# Sheet1.net
KiCad netlist of a schematic drawn in Altium Designer
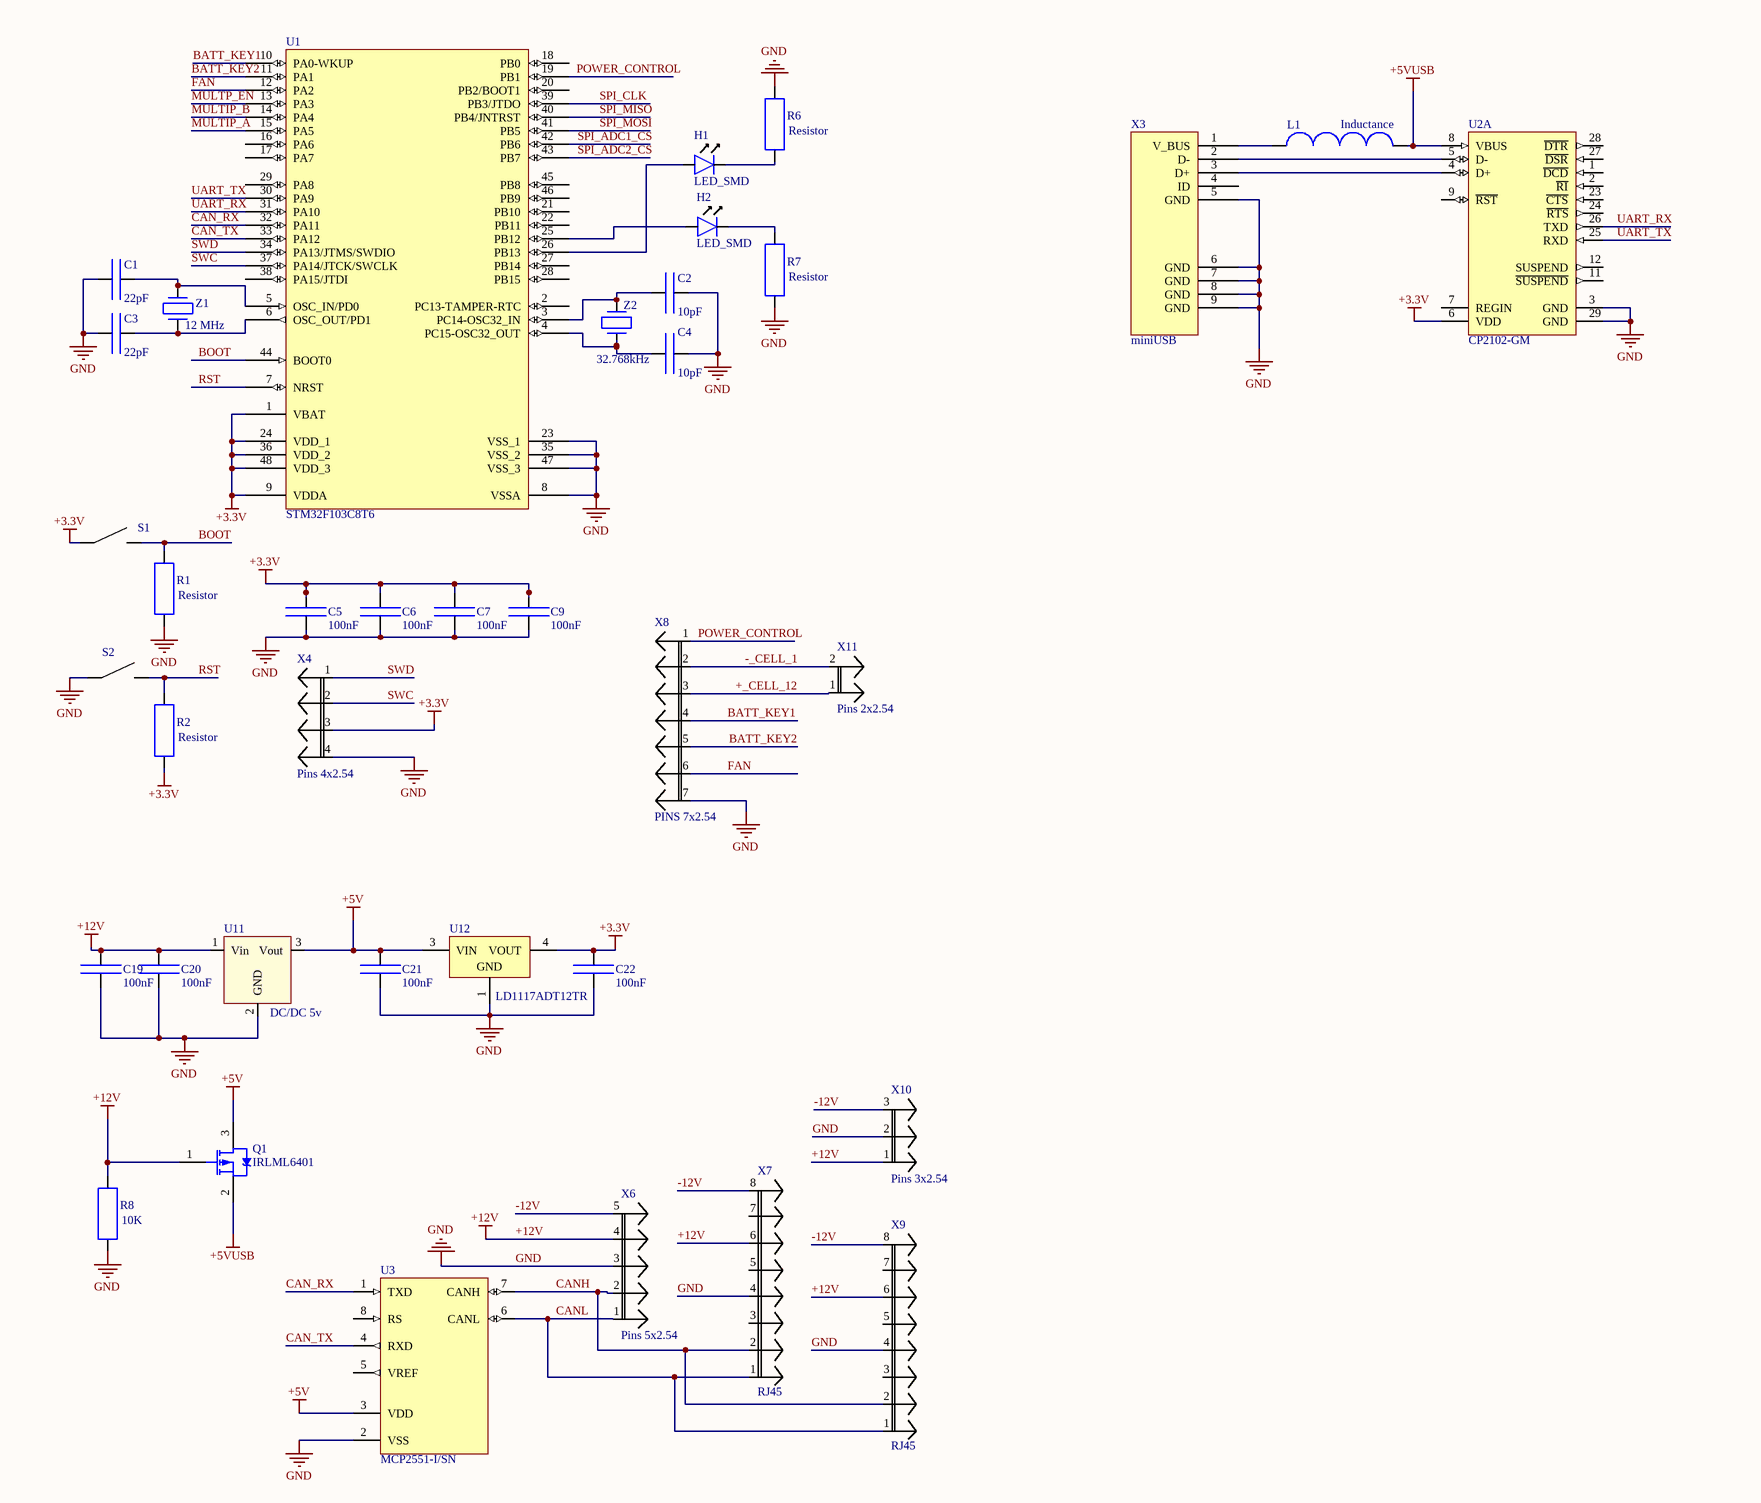
[diagram p0: Sheet1.SchDoc, top]
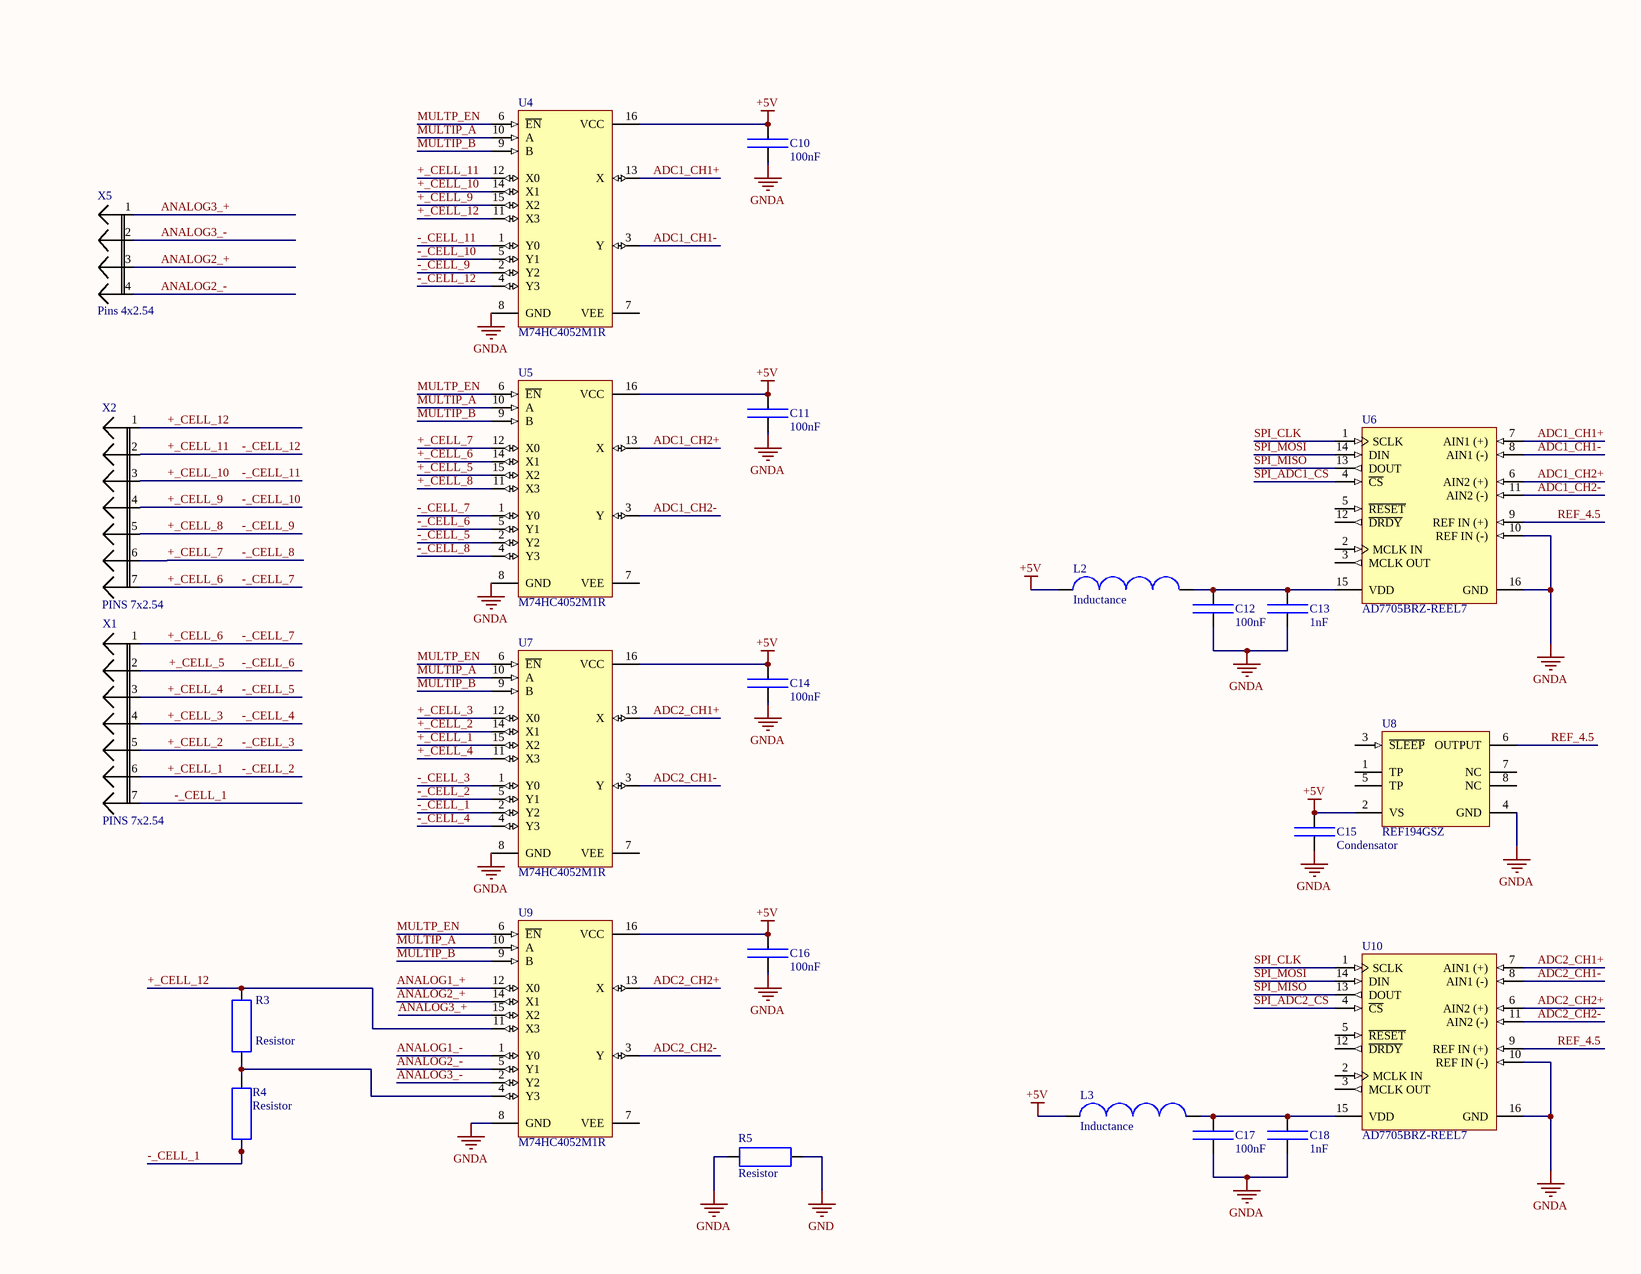
[diagram p1: Sheet1.SchDoc, bottom]

(export (version "E")
  (design (tool "Eeschema 10.0.6"))
  (components
    (comp (ref "C1") (value "22pF") (footprint "C0805") (libsource (lib "A_H_sch_lib") (part "Condensator")))
    (comp (ref "C2") (value "10pF") (footprint "C0805") (libsource (lib "A_H_sch_lib") (part "Condensator")))
    (comp (ref "C3") (value "22pF") (footprint "C0805") (libsource (lib "A_H_sch_lib") (part "Condensator")))
    (comp (ref "C4") (value "10pF") (footprint "C0805") (libsource (lib "A_H_sch_lib") (part "Condensator")))
    (comp (ref "C5") (value "100nF") (footprint "C0805") (libsource (lib "A_H_sch_lib") (part "Condensator")))
    (comp (ref "C6") (value "100nF") (footprint "C0805") (libsource (lib "A_H_sch_lib") (part "Condensator")))
    (comp (ref "C7") (value "100nF") (footprint "C0805") (libsource (lib "A_H_sch_lib") (part "Condensator")))
    (comp (ref "C9") (value "100nF") (footprint "C0805") (libsource (lib "A_H_sch_lib") (part "Condensator")))
    (comp (ref "C10")
      (value "100nF")
      (footprint "C0805")
      (libsource (lib "A_H_sch_lib") (part "Condensator"))
    )
    (comp (ref "C11")
      (value "100nF")
      (footprint "C0805")
      (libsource (lib "A_H_sch_lib") (part "Condensator"))
    )
    (comp (ref "C12")
      (value "100nF")
      (footprint "C0805")
      (libsource (lib "A_H_sch_lib") (part "Condensator"))
    )
    (comp (ref "C13") (value "1nF") (footprint "C0805") (libsource (lib "A_H_sch_lib") (part "Condensator")))
    (comp (ref "C14")
      (value "100nF")
      (footprint "C0805")
      (libsource (lib "A_H_sch_lib") (part "Condensator"))
    )
    (comp (ref "C15")
      (value "Condensator")
      (footprint "C0805")
      (libsource (lib "A_H_sch_lib") (part "Condensator"))
    )
    (comp (ref "C16")
      (value "100nF")
      (footprint "C0805")
      (libsource (lib "A_H_sch_lib") (part "Condensator"))
    )
    (comp (ref "C17")
      (value "100nF")
      (footprint "C0805")
      (libsource (lib "A_H_sch_lib") (part "Condensator"))
    )
    (comp (ref "C18") (value "1nF") (footprint "C0805") (libsource (lib "A_H_sch_lib") (part "Condensator")))
    (comp (ref "C19")
      (value "100nF")
      (footprint "C0805")
      (libsource (lib "A_H_sch_lib") (part "Condensator"))
    )
    (comp (ref "C20")
      (value "100nF")
      (footprint "C0805")
      (libsource (lib "A_H_sch_lib") (part "Condensator"))
    )
    (comp (ref "C21")
      (value "100nF")
      (footprint "C0805")
      (libsource (lib "A_H_sch_lib") (part "Condensator"))
    )
    (comp (ref "C22")
      (value "100nF")
      (footprint "C0805")
      (libsource (lib "A_H_sch_lib") (part "Condensator"))
    )
    (comp (ref "H1") (value "LED_SMD") (footprint "C0805") (libsource (lib "A_H_sch_lib") (part "LED_SMD")))
    (comp (ref "H2") (value "LED_SMD") (footprint "C0805") (libsource (lib "A_H_sch_lib") (part "LED_SMD")))
    (comp (ref "L1")
      (value "Inductance")
      (footprint "L0805")
      (libsource (lib "A_H_sch_lib") (part "Inductance"))
    )
    (comp (ref "L2")
      (value "Inductance")
      (footprint "L0805")
      (libsource (lib "A_H_sch_lib") (part "Inductance"))
    )
    (comp (ref "L3")
      (value "Inductance")
      (footprint "L0805")
      (libsource (lib "A_H_sch_lib") (part "Inductance"))
    )
    (comp (ref "Q1")
      (value "IRLML6401")
      (footprint "sot-23")
      (libsource (lib "A_H_sch_lib") (part "IRLML6401"))
    )
    (comp (ref "R1") (value "Resistor") (footprint "R0805") (libsource (lib "A_H_sch_lib") (part "Resistor")))
    (comp (ref "R2") (value "Resistor") (footprint "R0805") (libsource (lib "A_H_sch_lib") (part "Resistor")))
    (comp (ref "R3") (value "Resistor") (footprint "R0805") (libsource (lib "A_H_sch_lib") (part "Resistor")))
    (comp (ref "R4") (value "Resistor") (footprint "R0805") (libsource (lib "A_H_sch_lib") (part "Resistor")))
    (comp (ref "R5") (value "Resistor") (footprint "R0805") (libsource (lib "A_H_sch_lib") (part "Resistor")))
    (comp (ref "R6") (value "Resistor") (footprint "R0805") (libsource (lib "A_H_sch_lib") (part "Resistor")))
    (comp (ref "R7") (value "Resistor") (footprint "R0805") (libsource (lib "A_H_sch_lib") (part "Resistor")))
    (comp (ref "R8") (value "10K") (footprint "R0805") (libsource (lib "A_H_sch_lib") (part "Resistor")))
    (comp (ref "S1")
      (value "Tact_switch")
      (footprint "Tact_switch_smd")
      (libsource (lib "A_H_sch_lib") (part "Tact_switch"))
    )
    (comp (ref "S2")
      (value "Tact_switch")
      (footprint "Tact_switch_smd")
      (libsource (lib "A_H_sch_lib") (part "Tact_switch"))
    )
    (comp (ref "U1")
      (value "STM32F103C8T6")
      (footprint "LQFP48_N")
      (description "STM32 ARM-based 32-bit MCU with 64 Kbytes Flash, 48-pin LQFP, Industrial Temperature")
      (fields (field (name "PUBLISHER") "Altium Limited"))
      (libsource (lib "ST Microcontroller 32-Bit STM32") (part "STM32F103C8T6"))
    )
    (comp (ref "U2")
      (value "CP2102-GM")
      (footprint "SLAB-QFN-28-3125x3125TP_N")
      (description "Single-Chip USB to UART Bridge, 1024 Bytes EEPROM, -40 to 85 degC, 28-pin QFN, Tube")
      (fields (field (name "MANUFACTURER") "Silicon Labs"))
      (libsource (lib "Silicon Labs Interface") (part "CP2102-GM"))
    )
    (comp (ref "U3")
      (value "MCP2551-I/SN")
      (footprint "SOIC-SN8_N")
      (description "High-Speed CAN Transceiver, 8-Pin SOIC, Industrial Temperature")
      (fields (field (name "PUBLISHER") "Altium Limited"))
      (libsource (lib "Microchip Interface") (part "MCP2551-I/SN"))
    )
    (comp (ref "U4")
      (value "M74HC4052M1R")
      (footprint "SO16_N")
      (description "Analog Multiplexer/Demultiplexer Dual 4-Channel")
      (fields (field (name "PUBLISHER") "Altium Limited"))
      (libsource (lib "ST Logic Multiplexer") (part "M74HC4052M1R"))
    )
    (comp (ref "U5")
      (value "M74HC4052M1R")
      (footprint "SO16_N")
      (description "Analog Multiplexer/Demultiplexer Dual 4-Channel")
      (fields (field (name "PUBLISHER") "Altium Limited"))
      (libsource (lib "ST Logic Multiplexer") (part "M74HC4052M1R"))
    )
    (comp (ref "U6")
      (value "AD7705BRZ-REEL7")
      (footprint "RW-16_N")
      (fields (field (name "GENERIC PART NUMBER") "AD7705") (field (name "MANUFACTURER") "Analog Devices"))
      (libsource (lib "Analog Devices Data Converters Analog-to-Digital Converters") (part "AD7705BRZ-REEL7"))
    )
    (comp (ref "U7")
      (value "M74HC4052M1R")
      (footprint "SO16_N")
      (description "Analog Multiplexer/Demultiplexer Dual 4-Channel")
      (fields (field (name "PUBLISHER") "Altium Limited"))
      (libsource (lib "ST Logic Multiplexer") (part "M74HC4052M1R"))
    )
    (comp (ref "U8")
      (value "REF194GSZ")
      (footprint "ADI-R-8_N")
      (fields (field (name "MANUFACTURER") "Analog Devices"))
      (libsource (lib "Analog Devices Amplifiers and Linear Voltage References") (part "REF194GSZ"))
    )
    (comp (ref "U9")
      (value "M74HC4052M1R")
      (footprint "SO16_N")
      (description "Analog Multiplexer/Demultiplexer Dual 4-Channel")
      (fields (field (name "PUBLISHER") "Altium Limited"))
      (libsource (lib "ST Logic Multiplexer") (part "M74HC4052M1R"))
    )
    (comp (ref "U10")
      (value "AD7705BRZ-REEL7")
      (footprint "RW-16_N")
      (fields (field (name "GENERIC PART NUMBER") "AD7705") (field (name "MANUFACTURER") "Analog Devices"))
      (libsource (lib "Analog Devices Data Converters Analog-to-Digital Converters") (part "AD7705BRZ-REEL7"))
    )
    (comp (ref "U11")
      (value "DC/DC 5v")
      (footprint "A_H_pcb_lib:DC/DC R-78E")
      (libsource (lib "A_H_sch_lib") (part "DC/DC R-78E"))
    )
    (comp (ref "U12")
      (value "LD1117ADT12TR")
      (footprint "TO-252_N")
      (description "1A, Low Drop Positive Voltage Regulator, 1.2V, 3-Pin DPAK, Tape and Reel")
      (libsource (lib "STMicroelectronics Power Management Linear Regulator") (part "LD1117ADT12TR"))
    )
    (comp (ref "X1")
      (value "PINS 7x2.54")
      (footprint "A_H_pcb_lib:PINS 7X2.54")
      (libsource (lib "A_H_sch_lib") (part "PINS 7x2.54"))
    )
    (comp (ref "X2")
      (value "PINS 7x2.54")
      (footprint "A_H_pcb_lib:PINS 7X2.54")
      (libsource (lib "A_H_sch_lib") (part "PINS 7x2.54"))
    )
    (comp (ref "X3")
      (value "miniUSB")
      (footprint "A_H_pcb_lib:miniUSB")
      (libsource (lib "A_H_sch_lib") (part "miniUSB"))
    )
    (comp (ref "X4")
      (value "Pins 4x2.54")
      (footprint "Pins 4x2.54")
      (libsource (lib "A_H_sch_lib") (part "Pins 4x2.54"))
    )
    (comp (ref "X5")
      (value "Pins 4x2.54")
      (footprint "Pins 4x2.54")
      (libsource (lib "A_H_sch_lib") (part "Pins 4x2.54"))
    )
    (comp (ref "X6")
      (value "Pins 5x2.54")
      (footprint "Pins 5x2.54")
      (libsource (lib "A_H_sch_lib") (part "Pins 5x2.54"))
    )
    (comp (ref "X7")
      (value "RJ45")
      (footprint "A_H_pcb_lib:RJ45")
      (libsource (lib "A_H_sch_lib") (part "RJ45"))
    )
    (comp (ref "X8")
      (value "PINS 7x2.54")
      (footprint "PINS 7X2.54")
      (libsource (lib "") (part "PINS 7x2.54_1"))
    )
    (comp (ref "X9")
      (value "RJ45")
      (footprint "A_H_pcb_lib:RJ45")
      (libsource (lib "A_H_sch_lib") (part "RJ45"))
    )
    (comp (ref "X10")
      (value "Pins 3x2.54")
      (footprint "Pins 3x2.54")
      (libsource (lib "A_H_sch_lib") (part "Pins 3x2.54"))
    )
    (comp (ref "X11")
      (value "Pins 2x2.54")
      (footprint "Pins 2x2.54")
      (libsource (lib "A_H_sch_lib") (part "Pins 2x2.54"))
    )
    (comp (ref "Z1")
      (value "12 MHz")
      (footprint "kx 13 12MHz")
      (libsource (lib "A_H_sch_lib") (part "KX 13 Geyer"))
    )
    (comp (ref "Z2")
      (value "32.768kHz")
      (footprint "Geyer KX - 327S 32.768kHz")
      (libsource (lib "A_H_sch_lib") (part "Crystal Oscillator"))
    )
  )
  (nets
    (net (code "1") (name "+3.3V") (class "Default")
      (node (ref "C22") (pin "2") (pinfunction "2_2") (pintype "passive"))
      (node (ref "C5") (pin "2") (pinfunction "2_2") (pintype "passive"))
      (node (ref "C6") (pin "2") (pinfunction "2_2") (pintype "passive"))
      (node (ref "C7") (pin "2") (pinfunction "2_2") (pintype "passive"))
      (node (ref "C9") (pin "2") (pinfunction "2_2") (pintype "passive"))
      (node (ref "R2") (pin "1") (pinfunction "1_1") (pintype "passive"))
      (node (ref "S1") (pin "1") (pinfunction "11_1") (pintype "passive"))
      (node (ref "U1") (pin "1") (pinfunction "VBAT_1") (pintype "power_in"))
      (node (ref "U1") (pin "24") (pinfunction "VDD_1_24") (pintype "power_in"))
      (node (ref "U1") (pin "36") (pinfunction "VDD_2_36") (pintype "power_in"))
      (node (ref "U1") (pin "48") (pinfunction "VDD_3_48") (pintype "power_in"))
      (node (ref "U1") (pin "9") (pinfunction "VDDA_9") (pintype "power_in"))
      (node (ref "U12") (pin "4") (pinfunction "VOUT_4") (pintype "power_in"))
      (node (ref "U2") (pin "6") (pinfunction "VDD_6") (pintype "power_in"))
      (node (ref "X4") (pin "3") (pinfunction "3_3") (pintype "passive"))
    )
    (net (code "2") (name "+5V") (class "Default")
      (node (ref "C10") (pin "1") (pinfunction "1_1") (pintype "passive"))
      (node (ref "C11") (pin "1") (pinfunction "1_1") (pintype "passive"))
      (node (ref "C14") (pin "1") (pinfunction "1_1") (pintype "passive"))
      (node (ref "C15") (pin "1") (pinfunction "1_1") (pintype "passive"))
      (node (ref "C16") (pin "1") (pinfunction "1_1") (pintype "passive"))
      (node (ref "C21") (pin "2") (pinfunction "2_2") (pintype "passive"))
      (node (ref "L2") (pin "1") (pinfunction "1_1") (pintype "passive"))
      (node (ref "L3") (pin "1") (pinfunction "1_1") (pintype "passive"))
      (node (ref "Q1") (pin "3") (pinfunction "D_3") (pintype "passive"))
      (node (ref "U11") (pin "3") (pinfunction "Vout_3") (pintype "passive"))
      (node (ref "U12") (pin "3") (pinfunction "VIN_3") (pintype "power_in"))
      (node (ref "U3") (pin "3") (pinfunction "VDD_3") (pintype "power_in"))
      (node (ref "U4") (pin "16") (pinfunction "VCC_16") (pintype "power_in"))
      (node (ref "U5") (pin "16") (pinfunction "VCC_16") (pintype "power_in"))
      (node (ref "U7") (pin "16") (pinfunction "VCC_16") (pintype "power_in"))
      (node (ref "U8") (pin "2") (pinfunction "VS_2") (pintype "power_in"))
      (node (ref "U9") (pin "16") (pinfunction "VCC_16") (pintype "power_in"))
    )
    (net (code "3") (name "+5VUSB") (class "Default")
      (node (ref "L1") (pin "2") (pinfunction "2_2") (pintype "passive"))
      (node (ref "Q1") (pin "2") (pinfunction "S_2") (pintype "passive"))
      (node (ref "U2") (pin "8") (pinfunction "VBUS_8") (pintype "input"))
    )
    (net (code "4") (name "+12V") (class "Default")
      (node (ref "C19") (pin "2") (pinfunction "2_2") (pintype "passive"))
      (node (ref "C20") (pin "2") (pinfunction "2_2") (pintype "passive"))
      (node (ref "Q1") (pin "1") (pinfunction "G_1") (pintype "passive"))
      (node (ref "R8") (pin "2") (pinfunction "2_2") (pintype "passive"))
      (node (ref "U11") (pin "1") (pinfunction "Vin_1") (pintype "passive"))
      (node (ref "X10") (pin "1") (pinfunction "1_1") (pintype "passive"))
      (node (ref "X6") (pin "4") (pinfunction "4_4") (pintype "passive"))
      (node (ref "X7") (pin "6") (pinfunction "6_6") (pintype "passive"))
      (node (ref "X9") (pin "6") (pinfunction "6_6") (pintype "passive"))
    )
    (net (code "5") (name "/+_CELL_1") (class "Default")
      (node (ref "U7") (pin "15") (pinfunction "X2_15") (pintype "bidirectional"))
      (node (ref "U7") (pin "5") (pinfunction "Y1_5") (pintype "bidirectional"))
      (node (ref "X1") (pin "6") (pinfunction "6_6") (pintype "passive"))
    )
    (net (code "6") (name "/+_CELL_2") (class "Default")
      (node (ref "U7") (pin "1") (pinfunction "Y0_1") (pintype "bidirectional"))
      (node (ref "U7") (pin "14") (pinfunction "X1_14") (pintype "bidirectional"))
      (node (ref "X1") (pin "5") (pinfunction "5_5") (pintype "passive"))
    )
    (net (code "7") (name "/+_CELL_3") (class "Default")
      (node (ref "U7") (pin "12") (pinfunction "X0_12") (pintype "bidirectional"))
      (node (ref "U7") (pin "4") (pinfunction "Y3_4") (pintype "bidirectional"))
      (node (ref "X1") (pin "4") (pinfunction "4_4") (pintype "passive"))
    )
    (net (code "8") (name "/+_CELL_4") (class "Default")
      (node (ref "U5") (pin "2") (pinfunction "Y2_2") (pintype "bidirectional"))
      (node (ref "U7") (pin "11") (pinfunction "X3_11") (pintype "bidirectional"))
      (node (ref "X1") (pin "3") (pinfunction "3_3") (pintype "passive"))
    )
    (net (code "9") (name "/+_CELL_5") (class "Default")
      (node (ref "U5") (pin "15") (pinfunction "X2_15") (pintype "bidirectional"))
      (node (ref "U5") (pin "5") (pinfunction "Y1_5") (pintype "bidirectional"))
      (node (ref "X1") (pin "2") (pinfunction "2_2") (pintype "passive"))
    )
    (net (code "10") (name "/+_CELL_6") (class "Default")
      (node (ref "U5") (pin "1") (pinfunction "Y0_1") (pintype "bidirectional"))
      (node (ref "U5") (pin "14") (pinfunction "X1_14") (pintype "bidirectional"))
      (node (ref "X1") (pin "1") (pinfunction "1_1") (pintype "passive"))
      (node (ref "X2") (pin "7") (pinfunction "7_7") (pintype "passive"))
    )
    (net (code "11") (name "/+_CELL_7") (class "Default")
      (node (ref "U5") (pin "12") (pinfunction "X0_12") (pintype "bidirectional"))
      (node (ref "U5") (pin "4") (pinfunction "Y3_4") (pintype "bidirectional"))
      (node (ref "X2") (pin "6") (pinfunction "6_6") (pintype "passive"))
    )
    (net (code "12") (name "/+_CELL_8") (class "Default")
      (node (ref "U4") (pin "2") (pinfunction "Y2_2") (pintype "bidirectional"))
      (node (ref "U5") (pin "11") (pinfunction "X3_11") (pintype "bidirectional"))
      (node (ref "X2") (pin "5") (pinfunction "5_5") (pintype "passive"))
    )
    (net (code "13") (name "/+_CELL_9") (class "Default")
      (node (ref "U4") (pin "15") (pinfunction "X2_15") (pintype "bidirectional"))
      (node (ref "U4") (pin "5") (pinfunction "Y1_5") (pintype "bidirectional"))
      (node (ref "X2") (pin "4") (pinfunction "4_4") (pintype "passive"))
    )
    (net (code "14") (name "/+_CELL_10") (class "Default")
      (node (ref "U4") (pin "1") (pinfunction "Y0_1") (pintype "bidirectional"))
      (node (ref "U4") (pin "14") (pinfunction "X1_14") (pintype "bidirectional"))
      (node (ref "X2") (pin "3") (pinfunction "3_3") (pintype "passive"))
    )
    (net (code "15") (name "/+_CELL_11") (class "Default")
      (node (ref "U4") (pin "12") (pinfunction "X0_12") (pintype "bidirectional"))
      (node (ref "U4") (pin "4") (pinfunction "Y3_4") (pintype "bidirectional"))
      (node (ref "X2") (pin "2") (pinfunction "2_2") (pintype "passive"))
    )
    (net (code "16") (name "/+_CELL_12") (class "Default")
      (node (ref "R3") (pin "2") (pinfunction "2_2") (pintype "passive"))
      (node (ref "U4") (pin "11") (pinfunction "X3_11") (pintype "bidirectional"))
      (node (ref "U9") (pin "11") (pinfunction "X3_11") (pintype "bidirectional"))
      (node (ref "X11") (pin "1") (pinfunction "1_1") (pintype "passive"))
      (node (ref "X2") (pin "1") (pinfunction "1_1") (pintype "passive"))
      (node (ref "X8") (pin "3") (pinfunction "3_3") (pintype "passive"))
    )
    (net (code "17") (name "/-12V") (class "Default")
      (node (ref "X10") (pin "3") (pinfunction "3_3") (pintype "passive"))
      (node (ref "X6") (pin "5") (pinfunction "5_5") (pintype "passive"))
      (node (ref "X7") (pin "8") (pinfunction "8_8") (pintype "passive"))
      (node (ref "X9") (pin "8") (pinfunction "8_8") (pintype "passive"))
    )
    (net (code "18") (name "/-_CELL_1") (class "Default")
      (node (ref "R4") (pin "1") (pinfunction "1_1") (pintype "passive"))
      (node (ref "U7") (pin "2") (pinfunction "Y2_2") (pintype "bidirectional"))
      (node (ref "X1") (pin "7") (pinfunction "7_7") (pintype "passive"))
      (node (ref "X11") (pin "2") (pinfunction "2_2") (pintype "passive"))
      (node (ref "X8") (pin "2") (pinfunction "2_2") (pintype "passive"))
    )
    (net (code "19") (name "/ADC1_CH1+") (class "Default")
      (node (ref "U4") (pin "13") (pinfunction "X_13") (pintype "bidirectional"))
      (node (ref "U6") (pin "7") (pinfunction "AIN1_(+)_7") (pintype "input"))
    )
    (net (code "20") (name "/ADC1_CH1-") (class "Default")
      (node (ref "U4") (pin "3") (pinfunction "Y_3") (pintype "bidirectional"))
      (node (ref "U6") (pin "8") (pinfunction "AIN1_(-)_8") (pintype "input"))
    )
    (net (code "21") (name "/ADC1_CH2+") (class "Default")
      (node (ref "U5") (pin "13") (pinfunction "X_13") (pintype "bidirectional"))
      (node (ref "U6") (pin "6") (pinfunction "AIN2_(+)_6") (pintype "input"))
    )
    (net (code "22") (name "/ADC1_CH2-") (class "Default")
      (node (ref "U5") (pin "3") (pinfunction "Y_3") (pintype "bidirectional"))
      (node (ref "U6") (pin "11") (pinfunction "AIN2_(-)_11") (pintype "input"))
    )
    (net (code "23") (name "/ADC2_CH1+") (class "Default")
      (node (ref "U10") (pin "7") (pinfunction "AIN1_(+)_7") (pintype "input"))
      (node (ref "U7") (pin "13") (pinfunction "X_13") (pintype "bidirectional"))
    )
    (net (code "24") (name "/ADC2_CH1-") (class "Default")
      (node (ref "U10") (pin "8") (pinfunction "AIN1_(-)_8") (pintype "input"))
      (node (ref "U7") (pin "3") (pinfunction "Y_3") (pintype "bidirectional"))
    )
    (net (code "25") (name "/ADC2_CH2+") (class "Default")
      (node (ref "U10") (pin "6") (pinfunction "AIN2_(+)_6") (pintype "input"))
      (node (ref "U9") (pin "13") (pinfunction "X_13") (pintype "bidirectional"))
    )
    (net (code "26") (name "/ADC2_CH2-") (class "Default")
      (node (ref "U10") (pin "11") (pinfunction "AIN2_(-)_11") (pintype "input"))
      (node (ref "U9") (pin "3") (pinfunction "Y_3") (pintype "bidirectional"))
    )
    (net (code "27") (name "/ANALOG1_+") (class "Default")
      (node (ref "U9") (pin "12") (pinfunction "X0_12") (pintype "bidirectional"))
    )
    (net (code "28") (name "/ANALOG1_-") (class "Default")
      (node (ref "U9") (pin "1") (pinfunction "Y0_1") (pintype "bidirectional"))
    )
    (net (code "29") (name "/ANALOG2_+") (class "Default")
      (node (ref "U9") (pin "14") (pinfunction "X1_14") (pintype "bidirectional"))
      (node (ref "X5") (pin "3") (pinfunction "3_3") (pintype "passive"))
    )
    (net (code "30") (name "/ANALOG2_-") (class "Default")
      (node (ref "U9") (pin "5") (pinfunction "Y1_5") (pintype "bidirectional"))
      (node (ref "X5") (pin "4") (pinfunction "4_4") (pintype "passive"))
    )
    (net (code "31") (name "/ANALOG3_+") (class "Default")
      (node (ref "U9") (pin "15") (pinfunction "X2_15") (pintype "bidirectional"))
      (node (ref "X5") (pin "1") (pinfunction "1_1") (pintype "passive"))
    )
    (net (code "32") (name "/ANALOG3_-") (class "Default")
      (node (ref "U9") (pin "2") (pinfunction "Y2_2") (pintype "bidirectional"))
      (node (ref "X5") (pin "2") (pinfunction "2_2") (pintype "passive"))
    )
    (net (code "33") (name "/BATT_KEY1") (class "Default")
      (node (ref "U1") (pin "10") (pinfunction "PA0-WKUP_10") (pintype "bidirectional"))
      (node (ref "X8") (pin "4") (pinfunction "4_4") (pintype "passive"))
    )
    (net (code "34") (name "/BATT_KEY2") (class "Default")
      (node (ref "U1") (pin "11") (pinfunction "PA1_11") (pintype "bidirectional"))
      (node (ref "X8") (pin "5") (pinfunction "5_5") (pintype "passive"))
    )
    (net (code "35") (name "/BOOT") (class "Default")
      (node (ref "R1") (pin "2") (pinfunction "2_2") (pintype "passive"))
      (node (ref "S1") (pin "2") (pinfunction "12_2") (pintype "passive"))
      (node (ref "U1") (pin "44") (pinfunction "BOOT0_44") (pintype "input"))
    )
    (net (code "36") (name "/CANH") (class "Default")
      (node (ref "U3") (pin "7") (pinfunction "CANH_7") (pintype "bidirectional"))
      (node (ref "X6") (pin "2") (pinfunction "2_2") (pintype "passive"))
      (node (ref "X7") (pin "2") (pinfunction "2_2") (pintype "passive"))
      (node (ref "X9") (pin "2") (pinfunction "2_2") (pintype "passive"))
    )
    (net (code "37") (name "/CANL") (class "Default")
      (node (ref "U3") (pin "6") (pinfunction "CANL_6") (pintype "bidirectional"))
      (node (ref "X6") (pin "1") (pinfunction "1_1") (pintype "passive"))
      (node (ref "X7") (pin "1") (pinfunction "1_1") (pintype "passive"))
      (node (ref "X9") (pin "1") (pinfunction "1_1") (pintype "passive"))
    )
    (net (code "38") (name "/CAN_RX") (class "Default")
      (node (ref "U1") (pin "32") (pinfunction "PA11_32") (pintype "bidirectional"))
      (node (ref "U3") (pin "1") (pinfunction "TXD_1") (pintype "input"))
    )
    (net (code "39") (name "/CAN_TX") (class "Default")
      (node (ref "U1") (pin "33") (pinfunction "PA12_33") (pintype "bidirectional"))
      (node (ref "U3") (pin "4") (pinfunction "RXD_4") (pintype "output"))
    )
    (net (code "40") (name "/FAN") (class "Default")
      (node (ref "U1") (pin "12") (pinfunction "PA2_12") (pintype "bidirectional"))
      (node (ref "X8") (pin "6") (pinfunction "6_6") (pintype "passive"))
    )
    (net (code "41") (name "/MULTIP_A") (class "Default")
      (node (ref "U1") (pin "15") (pinfunction "PA5_15") (pintype "bidirectional"))
      (node (ref "U4") (pin "10") (pinfunction "A_10") (pintype "input"))
      (node (ref "U5") (pin "10") (pinfunction "A_10") (pintype "input"))
      (node (ref "U7") (pin "10") (pinfunction "A_10") (pintype "input"))
      (node (ref "U9") (pin "10") (pinfunction "A_10") (pintype "input"))
    )
    (net (code "42") (name "/MULTIP_B") (class "Default")
      (node (ref "U1") (pin "14") (pinfunction "PA4_14") (pintype "bidirectional"))
      (node (ref "U4") (pin "9") (pinfunction "B_9") (pintype "input"))
      (node (ref "U5") (pin "9") (pinfunction "B_9") (pintype "input"))
      (node (ref "U7") (pin "9") (pinfunction "B_9") (pintype "input"))
      (node (ref "U9") (pin "9") (pinfunction "B_9") (pintype "input"))
    )
    (net (code "43") (name "/MULTP_EN") (class "Default")
      (node (ref "U1") (pin "13") (pinfunction "PA3_13") (pintype "bidirectional"))
      (node (ref "U4") (pin "6") (pinfunction "~{EN}_6") (pintype "input"))
      (node (ref "U5") (pin "6") (pinfunction "~{EN}_6") (pintype "input"))
      (node (ref "U7") (pin "6") (pinfunction "~{EN}_6") (pintype "input"))
      (node (ref "U9") (pin "6") (pinfunction "~{EN}_6") (pintype "input"))
    )
    (net (code "44") (name "/POWER_CONTROL") (class "Default")
      (node (ref "U1") (pin "19") (pinfunction "PB1_19") (pintype "bidirectional"))
      (node (ref "X8") (pin "1") (pinfunction "1_1") (pintype "passive"))
    )
    (net (code "45") (name "/REF_4.5") (class "Default")
      (node (ref "U10") (pin "9") (pinfunction "REF_IN_(+)_9") (pintype "input"))
      (node (ref "U6") (pin "9") (pinfunction "REF_IN_(+)_9") (pintype "input"))
      (node (ref "U8") (pin "6") (pinfunction "OUTPUT_6") (pintype "tri_state"))
    )
    (net (code "46") (name "/RST") (class "Default")
      (node (ref "R2") (pin "2") (pinfunction "2_2") (pintype "passive"))
      (node (ref "S2") (pin "2") (pinfunction "12_2") (pintype "passive"))
      (node (ref "U1") (pin "7") (pinfunction "NRST_7") (pintype "bidirectional"))
    )
    (net (code "47") (name "/SPI_ADC1_CS") (class "Default")
      (node (ref "U1") (pin "42") (pinfunction "PB6_42") (pintype "bidirectional"))
      (node (ref "U6") (pin "4") (pinfunction "~{CS}_4") (pintype "input"))
    )
    (net (code "48") (name "/SPI_ADC2_CS") (class "Default")
      (node (ref "U1") (pin "43") (pinfunction "PB7_43") (pintype "bidirectional"))
      (node (ref "U10") (pin "4") (pinfunction "~{CS}_4") (pintype "input"))
    )
    (net (code "49") (name "/SPI_CLK") (class "Default")
      (node (ref "U1") (pin "39") (pinfunction "PB3/JTDO_39") (pintype "bidirectional"))
      (node (ref "U10") (pin "1") (pinfunction "SCLK_1") (pintype "input"))
      (node (ref "U6") (pin "1") (pinfunction "SCLK_1") (pintype "input"))
    )
    (net (code "50") (name "/SPI_MISO") (class "Default")
      (node (ref "U1") (pin "40") (pinfunction "PB4/JNTRST_40") (pintype "bidirectional"))
      (node (ref "U10") (pin "13") (pinfunction "DOUT_13") (pintype "output"))
      (node (ref "U6") (pin "13") (pinfunction "DOUT_13") (pintype "output"))
    )
    (net (code "51") (name "/SPI_MOSI") (class "Default")
      (node (ref "U1") (pin "41") (pinfunction "PB5_41") (pintype "bidirectional"))
      (node (ref "U10") (pin "14") (pinfunction "DIN_14") (pintype "input"))
      (node (ref "U6") (pin "14") (pinfunction "DIN_14") (pintype "input"))
    )
    (net (code "52") (name "/SWC") (class "Default")
      (node (ref "U1") (pin "37") (pinfunction "PA14/JTCK/SWCLK_37") (pintype "bidirectional"))
      (node (ref "X4") (pin "2") (pinfunction "2_2") (pintype "passive"))
    )
    (net (code "53") (name "/SWD") (class "Default")
      (node (ref "U1") (pin "34") (pinfunction "PA13/JTMS/SWDIO_34") (pintype "bidirectional"))
      (node (ref "X4") (pin "1") (pinfunction "1_1") (pintype "passive"))
    )
    (net (code "54") (name "/UART_RX") (class "Default")
      (node (ref "U1") (pin "31") (pinfunction "PA10_31") (pintype "bidirectional"))
      (node (ref "U2") (pin "26") (pinfunction "TXD_26") (pintype "output"))
    )
    (net (code "55") (name "/UART_TX") (class "Default")
      (node (ref "U1") (pin "30") (pinfunction "PA9_30") (pintype "bidirectional"))
      (node (ref "U2") (pin "25") (pinfunction "RXD_25") (pintype "input"))
    )
    (net (code "56") (name "GND") (class "Default")
      (node (ref "C1") (pin "1") (pinfunction "1_1") (pintype "passive"))
      (node (ref "C19") (pin "1") (pinfunction "1_1") (pintype "passive"))
      (node (ref "C2") (pin "1") (pinfunction "1_1") (pintype "passive"))
      (node (ref "C20") (pin "1") (pinfunction "1_1") (pintype "passive"))
      (node (ref "C21") (pin "1") (pinfunction "1_1") (pintype "passive"))
      (node (ref "C22") (pin "1") (pinfunction "1_1") (pintype "passive"))
      (node (ref "C3") (pin "1") (pinfunction "1_1") (pintype "passive"))
      (node (ref "C4") (pin "1") (pinfunction "1_1") (pintype "passive"))
      (node (ref "C5") (pin "1") (pinfunction "1_1") (pintype "passive"))
      (node (ref "C6") (pin "1") (pinfunction "1_1") (pintype "passive"))
      (node (ref "C7") (pin "1") (pinfunction "1_1") (pintype "passive"))
      (node (ref "C9") (pin "1") (pinfunction "1_1") (pintype "passive"))
      (node (ref "R1") (pin "1") (pinfunction "1_1") (pintype "passive"))
      (node (ref "R5") (pin "1") (pinfunction "1_1") (pintype "passive"))
      (node (ref "R6") (pin "2") (pinfunction "2_2") (pintype "passive"))
      (node (ref "R7") (pin "1") (pinfunction "1_1") (pintype "passive"))
      (node (ref "R8") (pin "1") (pinfunction "1_1") (pintype "passive"))
      (node (ref "S2") (pin "1") (pinfunction "11_1") (pintype "passive"))
      (node (ref "U1") (pin "23") (pinfunction "VSS_1_23") (pintype "power_in"))
      (node (ref "U1") (pin "35") (pinfunction "VSS_2_35") (pintype "power_in"))
      (node (ref "U1") (pin "47") (pinfunction "VSS_3_47") (pintype "power_in"))
      (node (ref "U1") (pin "8") (pinfunction "VSSA_8") (pintype "power_in"))
      (node (ref "U11") (pin "2") (pinfunction "GND_2") (pintype "passive"))
      (node (ref "U12") (pin "1") (pinfunction "GND_1") (pintype "power_in"))
      (node (ref "U2") (pin "29") (pinfunction "GND_29") (pintype "power_in"))
      (node (ref "U2") (pin "3") (pinfunction "GND_3") (pintype "power_in"))
      (node (ref "U3") (pin "2") (pinfunction "VSS_2") (pintype "power_in"))
      (node (ref "X10") (pin "2") (pinfunction "2_2") (pintype "passive"))
      (node (ref "X3") (pin "5") (pinfunction "GND_5") (pintype "passive"))
      (node (ref "X3") (pin "6") (pinfunction "GND_6") (pintype "passive"))
      (node (ref "X3") (pin "7") (pinfunction "GND_7") (pintype "passive"))
      (node (ref "X3") (pin "8") (pinfunction "GND_8") (pintype "passive"))
      (node (ref "X3") (pin "9") (pinfunction "GND_9") (pintype "passive"))
      (node (ref "X4") (pin "4") (pinfunction "4_4") (pintype "passive"))
      (node (ref "X6") (pin "3") (pinfunction "3_3") (pintype "passive"))
      (node (ref "X7") (pin "4") (pinfunction "4_4") (pintype "passive"))
      (node (ref "X8") (pin "7") (pinfunction "7_7") (pintype "passive"))
      (node (ref "X9") (pin "4") (pinfunction "4_4") (pintype "passive"))
    )
    (net (code "57") (name "GNDA") (class "Default")
      (node (ref "C10") (pin "2") (pinfunction "2_2") (pintype "passive"))
      (node (ref "C11") (pin "2") (pinfunction "2_2") (pintype "passive"))
      (node (ref "C12") (pin "2") (pinfunction "2_2") (pintype "passive"))
      (node (ref "C13") (pin "2") (pinfunction "2_2") (pintype "passive"))
      (node (ref "C14") (pin "2") (pinfunction "2_2") (pintype "passive"))
      (node (ref "C15") (pin "2") (pinfunction "2_2") (pintype "passive"))
      (node (ref "C16") (pin "2") (pinfunction "2_2") (pintype "passive"))
      (node (ref "C17") (pin "2") (pinfunction "2_2") (pintype "passive"))
      (node (ref "C18") (pin "2") (pinfunction "2_2") (pintype "passive"))
      (node (ref "R5") (pin "2") (pinfunction "2_2") (pintype "passive"))
      (node (ref "U10") (pin "10") (pinfunction "REF_IN_(-)_10") (pintype "input"))
      (node (ref "U10") (pin "16") (pinfunction "GND_16") (pintype "power_in"))
      (node (ref "U4") (pin "8") (pinfunction "GND_8") (pintype "power_in"))
      (node (ref "U5") (pin "8") (pinfunction "GND_8") (pintype "power_in"))
      (node (ref "U6") (pin "10") (pinfunction "REF_IN_(-)_10") (pintype "input"))
      (node (ref "U6") (pin "16") (pinfunction "GND_16") (pintype "power_in"))
      (node (ref "U7") (pin "8") (pinfunction "GND_8") (pintype "power_in"))
      (node (ref "U8") (pin "4") (pinfunction "GND_4") (pintype "power_in"))
      (node (ref "U9") (pin "8") (pinfunction "GND_8") (pintype "power_in"))
    )
    (net (code "58") (name "Net-(H1-Pad2)") (class "Default")
      (node (ref "H1") (pin "2") (pinfunction "2_2") (pintype "passive"))
      (node (ref "R6") (pin "1") (pinfunction "1_1") (pintype "passive"))
    )
    (net (code "59") (name "Net-(H2-Pad2)") (class "Default")
      (node (ref "H2") (pin "2") (pinfunction "2_2") (pintype "passive"))
      (node (ref "R7") (pin "2") (pinfunction "2_2") (pintype "passive"))
    )
    (net (code "60") (name "Net-(U1-OSC_IN{slash}PD0)") (class "Default")
      (node (ref "C1") (pin "2") (pinfunction "2_2") (pintype "passive"))
      (node (ref "U1") (pin "5") (pinfunction "OSC_IN/PD0_5") (pintype "input"))
      (node (ref "Z1") (pin "1") (pinfunction "1_1") (pintype "passive"))
    )
    (net (code "61") (name "Net-(U1-OSC_OUT{slash}PD1)") (class "Default")
      (node (ref "C3") (pin "2") (pinfunction "2_2") (pintype "passive"))
      (node (ref "U1") (pin "6") (pinfunction "OSC_OUT/PD1_6") (pintype "output"))
      (node (ref "Z1") (pin "3") (pinfunction "3_3") (pintype "passive"))
    )
    (net (code "62") (name "Net-(U1-PB12)") (class "Default")
      (node (ref "H2") (pin "1") (pinfunction "1_1") (pintype "passive"))
      (node (ref "U1") (pin "25") (pinfunction "PB12_25") (pintype "bidirectional"))
    )
    (net (code "63") (name "Net-(U1-PB13)") (class "Default")
      (node (ref "H1") (pin "1") (pinfunction "1_1") (pintype "passive"))
      (node (ref "U1") (pin "26") (pinfunction "PB13_26") (pintype "bidirectional"))
    )
    (net (code "64") (name "Net-(U1-PC14-OSC32_IN)") (class "Default")
      (node (ref "C2") (pin "2") (pinfunction "2_2") (pintype "passive"))
      (node (ref "U1") (pin "3") (pinfunction "PC14-OSC32_IN_3") (pintype "bidirectional"))
      (node (ref "Z2") (pin "1") (pinfunction "1_1") (pintype "passive"))
    )
    (net (code "65") (name "Net-(U1-PC15-OSC32_OUT)") (class "Default")
      (node (ref "C4") (pin "2") (pinfunction "2_2") (pintype "passive"))
      (node (ref "U1") (pin "4") (pinfunction "PC15-OSC32_OUT_4") (pintype "bidirectional"))
      (node (ref "Z2") (pin "2") (pinfunction "2_2") (pintype "passive"))
    )
    (net (code "66") (name "Net-(U2A-D+)") (class "Default")
      (node (ref "U2") (pin "4") (pinfunction "D+_4") (pintype "bidirectional"))
      (node (ref "X3") (pin "3") (pinfunction "D+_3") (pintype "passive"))
    )
    (net (code "67") (name "Net-(U2A-D-)") (class "Default")
      (node (ref "U2") (pin "5") (pinfunction "D-_5") (pintype "bidirectional"))
      (node (ref "X3") (pin "2") (pinfunction "D-_2") (pintype "passive"))
    )
    (net (code "68") (name "Net-(U6-VDD)") (class "Default")
      (node (ref "C12") (pin "1") (pinfunction "1_1") (pintype "passive"))
      (node (ref "C13") (pin "1") (pinfunction "1_1") (pintype "passive"))
      (node (ref "L2") (pin "2") (pinfunction "2_2") (pintype "passive"))
      (node (ref "U6") (pin "15") (pinfunction "VDD_15") (pintype "power_in"))
    )
    (net (code "69") (name "Net-(U9-Y3)") (class "Default")
      (node (ref "R3") (pin "1") (pinfunction "1_1") (pintype "passive"))
      (node (ref "R4") (pin "2") (pinfunction "2_2") (pintype "passive"))
      (node (ref "U9") (pin "4") (pinfunction "Y3_4") (pintype "bidirectional"))
    )
    (net (code "70") (name "Net-(U10-VDD)") (class "Default")
      (node (ref "C17") (pin "1") (pinfunction "1_1") (pintype "passive"))
      (node (ref "C18") (pin "1") (pinfunction "1_1") (pintype "passive"))
      (node (ref "L3") (pin "2") (pinfunction "2_2") (pintype "passive"))
      (node (ref "U10") (pin "15") (pinfunction "VDD_15") (pintype "power_in"))
    )
    (net (code "71") (name "Net-(X3-V_BUS)") (class "Default")
      (node (ref "L1") (pin "1") (pinfunction "1_1") (pintype "passive"))
      (node (ref "X3") (pin "1") (pinfunction "V_BUS_1") (pintype "passive"))
    )
    (net (code "72") (name "unconnected-(U1-PA6-Pad16)") (class "Default")
      (node (ref "U1") (pin "16") (pinfunction "PA6_16") (pintype "bidirectional"))
    )
    (net (code "73") (name "unconnected-(U1-PA7-Pad17)") (class "Default")
      (node (ref "U1") (pin "17") (pinfunction "PA7_17") (pintype "bidirectional"))
    )
    (net (code "74") (name "unconnected-(U1-PA8-Pad29)") (class "Default")
      (node (ref "U1") (pin "29") (pinfunction "PA8_29") (pintype "bidirectional"))
    )
    (net (code "75") (name "unconnected-(U1-PA15{slash}JTDI-Pad38)") (class "Default")
      (node (ref "U1") (pin "38") (pinfunction "PA15/JTDI_38") (pintype "bidirectional"))
    )
    (net (code "76") (name "unconnected-(U1-PB0-Pad18)") (class "Default")
      (node (ref "U1") (pin "18") (pinfunction "PB0_18") (pintype "bidirectional"))
    )
    (net (code "77") (name "unconnected-(U1-PB2{slash}BOOT1-Pad20)") (class "Default")
      (node (ref "U1") (pin "20") (pinfunction "PB2/BOOT1_20") (pintype "bidirectional"))
    )
    (net (code "78") (name "unconnected-(U1-PB8-Pad45)") (class "Default")
      (node (ref "U1") (pin "45") (pinfunction "PB8_45") (pintype "bidirectional"))
    )
    (net (code "79") (name "unconnected-(U1-PB9-Pad46)") (class "Default")
      (node (ref "U1") (pin "46") (pinfunction "PB9_46") (pintype "bidirectional"))
    )
    (net (code "80") (name "unconnected-(U1-PB10-Pad21)") (class "Default")
      (node (ref "U1") (pin "21") (pinfunction "PB10_21") (pintype "bidirectional"))
    )
    (net (code "81") (name "unconnected-(U1-PB11-Pad22)") (class "Default")
      (node (ref "U1") (pin "22") (pinfunction "PB11_22") (pintype "bidirectional"))
    )
    (net (code "82") (name "unconnected-(U1-PB14-Pad27)") (class "Default")
      (node (ref "U1") (pin "27") (pinfunction "PB14_27") (pintype "bidirectional"))
    )
    (net (code "83") (name "unconnected-(U1-PB15-Pad28)") (class "Default")
      (node (ref "U1") (pin "28") (pinfunction "PB15_28") (pintype "bidirectional"))
    )
    (net (code "84") (name "unconnected-(U1-PC13-TAMPER-RTC-Pad2)") (class "Default")
      (node (ref "U1") (pin "2") (pinfunction "PC13-TAMPER-RTC_2") (pintype "bidirectional"))
    )
    (net (code "85") (name "unconnected-(U2A-REGIN-Pad7)") (class "Default")
      (node (ref "U2") (pin "7") (pinfunction "REGIN_7") (pintype "power_in"))
    )
    (net (code "86") (name "unconnected-(U2A-SUSPEND-Pad12)") (class "Default")
      (node (ref "U2") (pin "12") (pinfunction "SUSPEND_12") (pintype "output"))
    )
    (net (code "87") (name "unconnected-(U2A-~{CTS}-Pad23)") (class "Default")
      (node (ref "U2") (pin "23") (pinfunction "~{CTS}_23") (pintype "input"))
    )
    (net (code "88") (name "unconnected-(U2A-~{DCD}-Pad1)") (class "Default")
      (node (ref "U2") (pin "1") (pinfunction "~{DCD}_1") (pintype "input"))
    )
    (net (code "89") (name "unconnected-(U2A-~{DSR}-Pad27)") (class "Default")
      (node (ref "U2") (pin "27") (pinfunction "~{DSR}_27") (pintype "input"))
    )
    (net (code "90") (name "unconnected-(U2A-~{DTR}-Pad28)") (class "Default")
      (node (ref "U2") (pin "28") (pinfunction "~{DTR}_28") (pintype "output"))
    )
    (net (code "91") (name "unconnected-(U2A-~{RI}-Pad2)") (class "Default")
      (node (ref "U2") (pin "2") (pinfunction "~{RI}_2") (pintype "input"))
    )
    (net (code "92") (name "unconnected-(U2A-~{RST}-Pad9)") (class "Default")
      (node (ref "U2") (pin "9") (pinfunction "~{RST}_9") (pintype "bidirectional"))
    )
    (net (code "93") (name "unconnected-(U2A-~{RTS}-Pad24)") (class "Default")
      (node (ref "U2") (pin "24") (pinfunction "~{RTS}_24") (pintype "output"))
    )
    (net (code "94") (name "unconnected-(U2A-~{SUSPEND}-Pad11)") (class "Default")
      (node (ref "U2") (pin "11") (pinfunction "~{SUSPEND}_11") (pintype "output"))
    )
    (net (code "95") (name "unconnected-(U3-RS-Pad8)") (class "Default")
      (node (ref "U3") (pin "8") (pinfunction "RS_8") (pintype "input"))
    )
    (net (code "96") (name "unconnected-(U3-VREF-Pad5)") (class "Default")
      (node (ref "U3") (pin "5") (pinfunction "VREF_5") (pintype "output"))
    )
    (net (code "97") (name "unconnected-(U4-VEE-Pad7)") (class "Default")
      (node (ref "U4") (pin "7") (pinfunction "VEE_7") (pintype "power_in"))
    )
    (net (code "98") (name "unconnected-(U5-VEE-Pad7)") (class "Default")
      (node (ref "U5") (pin "7") (pinfunction "VEE_7") (pintype "power_in"))
    )
    (net (code "99") (name "unconnected-(U6-MCLK_IN-Pad2)") (class "Default")
      (node (ref "U6") (pin "2") (pinfunction "MCLK_IN_2") (pintype "input"))
    )
    (net (code "100") (name "unconnected-(U6-MCLK_OUT-Pad3)") (class "Default")
      (node (ref "U6") (pin "3") (pinfunction "MCLK_OUT_3") (pintype "output"))
    )
    (net (code "101") (name "unconnected-(U6-~{DRDY}-Pad12)") (class "Default")
      (node (ref "U6") (pin "12") (pinfunction "~{DRDY}_12") (pintype "output"))
    )
    (net (code "102") (name "unconnected-(U6-~{RESET}-Pad5)") (class "Default")
      (node (ref "U6") (pin "5") (pinfunction "~{RESET}_5") (pintype "input"))
    )
    (net (code "103") (name "unconnected-(U7-VEE-Pad7)") (class "Default")
      (node (ref "U7") (pin "7") (pinfunction "VEE_7") (pintype "power_in"))
    )
    (net (code "104") (name "unconnected-(U8-NC-Pad7)") (class "Default")
      (node (ref "U8") (pin "7") (pinfunction "NC_7") (pintype "passive"))
    )
    (net (code "105") (name "unconnected-(U8-NC-Pad8)") (class "Default")
      (node (ref "U8") (pin "8") (pinfunction "NC_8") (pintype "passive"))
    )
    (net (code "106") (name "unconnected-(U8-TP-Pad1)") (class "Default")
      (node (ref "U8") (pin "1") (pinfunction "TP_1") (pintype "passive"))
    )
    (net (code "107") (name "unconnected-(U8-TP-Pad5)") (class "Default")
      (node (ref "U8") (pin "5") (pinfunction "TP_5") (pintype "passive"))
    )
    (net (code "108") (name "unconnected-(U8-~{SLEEP}-Pad3)") (class "Default")
      (node (ref "U8") (pin "3") (pinfunction "~{SLEEP}_3") (pintype "input"))
    )
    (net (code "109") (name "unconnected-(U9-VEE-Pad7)") (class "Default")
      (node (ref "U9") (pin "7") (pinfunction "VEE_7") (pintype "power_in"))
    )
    (net (code "110") (name "unconnected-(U10-MCLK_IN-Pad2)") (class "Default")
      (node (ref "U10") (pin "2") (pinfunction "MCLK_IN_2") (pintype "input"))
    )
    (net (code "111") (name "unconnected-(U10-MCLK_OUT-Pad3)") (class "Default")
      (node (ref "U10") (pin "3") (pinfunction "MCLK_OUT_3") (pintype "output"))
    )
    (net (code "112") (name "unconnected-(U10-~{DRDY}-Pad12)") (class "Default")
      (node (ref "U10") (pin "12") (pinfunction "~{DRDY}_12") (pintype "output"))
    )
    (net (code "113") (name "unconnected-(U10-~{RESET}-Pad5)") (class "Default")
      (node (ref "U10") (pin "5") (pinfunction "~{RESET}_5") (pintype "input"))
    )
    (net (code "114") (name "unconnected-(X3-ID-Pad4)") (class "Default")
      (node (ref "X3") (pin "4") (pinfunction "ID_4") (pintype "passive"))
    )
    (net (code "115") (name "unconnected-(X7-Pad3)") (class "Default")
      (node (ref "X7") (pin "3") (pinfunction "3_3") (pintype "passive"))
    )
    (net (code "116") (name "unconnected-(X7-Pad5)") (class "Default")
      (node (ref "X7") (pin "5") (pinfunction "5_5") (pintype "passive"))
    )
    (net (code "117") (name "unconnected-(X7-Pad7)") (class "Default")
      (node (ref "X7") (pin "7") (pinfunction "7_7") (pintype "passive"))
    )
    (net (code "118") (name "unconnected-(X9-Pad3)") (class "Default")
      (node (ref "X9") (pin "3") (pinfunction "3_3") (pintype "passive"))
    )
    (net (code "119") (name "unconnected-(X9-Pad5)") (class "Default")
      (node (ref "X9") (pin "5") (pinfunction "5_5") (pintype "passive"))
    )
    (net (code "120") (name "unconnected-(X9-Pad7)") (class "Default")
      (node (ref "X9") (pin "7") (pinfunction "7_7") (pintype "passive"))
    )
  )
)
